# RSS.net
KiCad netlist of a schematic drawn in EAGLE
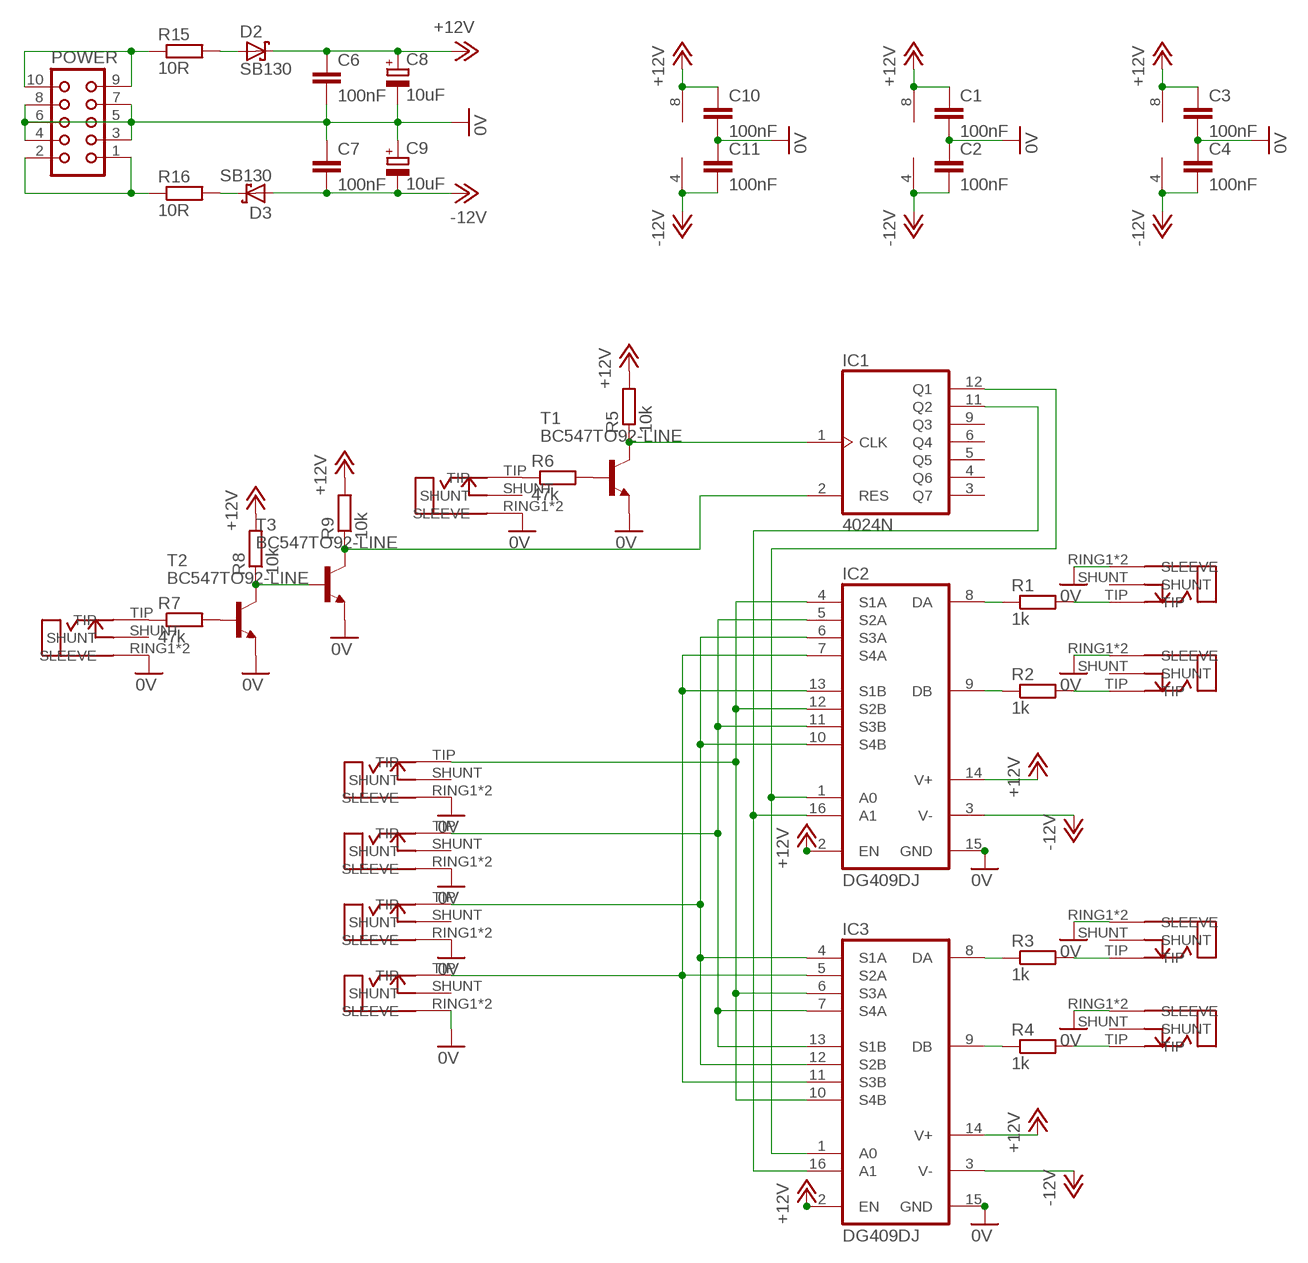
[diagram p0: schematic, sheet 1]

(export (version "E")
  (design (tool "Eeschema 10.0.6"))
  (components
    (comp (ref "C1")
      (value "100nF")
      (footprint "eagle-import:C025-024X044")
      (libsource (lib "eagle-import") (part "C-EU025-024X044"))
    )
    (comp (ref "C2")
      (value "100nF")
      (footprint "eagle-import:C025-024X044")
      (libsource (lib "eagle-import") (part "C-EU025-024X044"))
    )
    (comp (ref "C3")
      (value "100nF")
      (footprint "eagle-import:C025-024X044")
      (libsource (lib "eagle-import") (part "C-EU025-024X044"))
    )
    (comp (ref "C4")
      (value "100nF")
      (footprint "eagle-import:C025-024X044")
      (libsource (lib "eagle-import") (part "C-EU025-024X044"))
    )
    (comp (ref "C6")
      (value "100nF")
      (footprint "eagle-import:C025-024X044")
      (libsource (lib "eagle-import") (part "C-EU025-024X044"))
    )
    (comp (ref "C7")
      (value "100nF")
      (footprint "eagle-import:C025-024X044")
      (libsource (lib "eagle-import") (part "C-EU025-024X044"))
    )
    (comp (ref "C8")
      (value "10uF")
      (footprint "eagle-import:E2-5")
      (libsource (lib "eagle-import") (part "CPOL-EUE2-5"))
    )
    (comp (ref "C9")
      (value "10uF")
      (footprint "eagle-import:E2-5")
      (libsource (lib "eagle-import") (part "CPOL-EUE2-5"))
    )
    (comp (ref "C10")
      (value "100nF")
      (footprint "eagle-import:C025-024X044")
      (libsource (lib "eagle-import") (part "C-EU025-024X044"))
    )
    (comp (ref "C11")
      (value "100nF")
      (footprint "eagle-import:C025-024X044")
      (libsource (lib "eagle-import") (part "C-EU025-024X044"))
    )
    (comp (ref "CLOCK")
      (value "ERTHENVAR_3.5MM_JACKHOLES")
      (footprint "eagle-import:ERTHENVAR")
      (libsource (lib "eagle-import") (part "ERTHENVAR_3.5MM_JACKHOLES"))
    )
    (comp (ref "D2")
      (value "SB130")
      (footprint "eagle-import:DO41-7")
      (libsource (lib "eagle-import") (part "SB130DO-204AL"))
    )
    (comp (ref "D3")
      (value "SB130")
      (footprint "eagle-import:DO41-7")
      (libsource (lib "eagle-import") (part "SB130DO-204AL"))
    )
    (comp (ref "I/O1")
      (value "ERTHENVAR_3.5MM_JACKHOLES")
      (footprint "eagle-import:ERTHENVAR")
      (libsource (lib "eagle-import") (part "ERTHENVAR_3.5MM_JACKHOLES"))
    )
    (comp (ref "I/O2")
      (value "ERTHENVAR_3.5MM_JACKHOLES")
      (footprint "eagle-import:ERTHENVAR")
      (libsource (lib "eagle-import") (part "ERTHENVAR_3.5MM_JACKHOLES"))
    )
    (comp (ref "I/O3")
      (value "ERTHENVAR_3.5MM_JACKHOLES")
      (footprint "eagle-import:ERTHENVAR")
      (libsource (lib "eagle-import") (part "ERTHENVAR_3.5MM_JACKHOLES"))
    )
    (comp (ref "I/O4")
      (value "ERTHENVAR_3.5MM_JACKHOLES")
      (footprint "eagle-import:ERTHENVAR")
      (libsource (lib "eagle-import") (part "ERTHENVAR_3.5MM_JACKHOLES"))
    )
    (comp (ref "IC1")
      (value "4024N")
      (footprint "eagle-import:DIL14")
      (libsource (lib "eagle-import") (part "4024N"))
    )
    (comp (ref "IC2")
      (value "DG409DJ")
      (footprint "eagle-import:DIL16")
      (fields (field (name "MF") "INTERSIL"))
      (libsource (lib "eagle-import") (part "DG409DJ"))
    )
    (comp (ref "IC3")
      (value "DG409DJ")
      (footprint "eagle-import:DIL16")
      (fields (field (name "MF") "INTERSIL"))
      (libsource (lib "eagle-import") (part "DG409DJ"))
    )
    (comp (ref "IC4")
      (value "TL072")
      (footprint "eagle-import:DIL08")
      (libsource (lib "eagle-import") (part "TL072P"))
    )
    (comp (ref "IC5")
      (value "TL072")
      (footprint "eagle-import:DIL08")
      (libsource (lib "eagle-import") (part "TL072P"))
    )
    (comp (ref "IC6")
      (value "TL072")
      (footprint "eagle-import:DIL08")
      (libsource (lib "eagle-import") (part "TL072P"))
    )
    (comp (ref "O/I1")
      (value "ERTHENVAR_3.5MM_JACKHOLES")
      (footprint "eagle-import:ERTHENVAR")
      (libsource (lib "eagle-import") (part "ERTHENVAR_3.5MM_JACKHOLES"))
    )
    (comp (ref "O/I2")
      (value "ERTHENVAR_3.5MM_JACKHOLES")
      (footprint "eagle-import:ERTHENVAR")
      (libsource (lib "eagle-import") (part "ERTHENVAR_3.5MM_JACKHOLES"))
    )
    (comp (ref "O/I3")
      (value "ERTHENVAR_3.5MM_JACKHOLES")
      (footprint "eagle-import:ERTHENVAR")
      (libsource (lib "eagle-import") (part "ERTHENVAR_3.5MM_JACKHOLES"))
    )
    (comp (ref "O/I4")
      (value "ERTHENVAR_3.5MM_JACKHOLES")
      (footprint "eagle-import:ERTHENVAR")
      (libsource (lib "eagle-import") (part "ERTHENVAR_3.5MM_JACKHOLES"))
    )
    (comp (ref "POWER")
      (value "CON10L")
      (footprint "eagle-import:CON10L")
      (libsource (lib "eagle-import") (part "CON10L"))
    )
    (comp (ref "R1")
      (value "1k")
      (footprint "eagle-import:0207_9")
      (libsource (lib "eagle-import") (part "R-EU_0207/10"))
    )
    (comp (ref "R2")
      (value "1k")
      (footprint "eagle-import:0207_9")
      (libsource (lib "eagle-import") (part "R-EU_0207/10"))
    )
    (comp (ref "R3")
      (value "1k")
      (footprint "eagle-import:0207_9")
      (libsource (lib "eagle-import") (part "R-EU_0207/10"))
    )
    (comp (ref "R4")
      (value "1k")
      (footprint "eagle-import:0207_9")
      (libsource (lib "eagle-import") (part "R-EU_0207/10"))
    )
    (comp (ref "R5")
      (value "10k")
      (footprint "eagle-import:0207_9")
      (libsource (lib "eagle-import") (part "R-EU_0207/10"))
    )
    (comp (ref "R6")
      (value "47k")
      (footprint "eagle-import:0207_9")
      (libsource (lib "eagle-import") (part "R-EU_0207/10"))
    )
    (comp (ref "R7")
      (value "47k")
      (footprint "eagle-import:0207_9")
      (libsource (lib "eagle-import") (part "R-EU_0207/10"))
    )
    (comp (ref "R8")
      (value "10k")
      (footprint "eagle-import:0207_9")
      (libsource (lib "eagle-import") (part "R-EU_0207/10"))
    )
    (comp (ref "R9")
      (value "10k")
      (footprint "eagle-import:0207_9")
      (libsource (lib "eagle-import") (part "R-EU_0207/10"))
    )
    (comp (ref "R15")
      (value "10R")
      (footprint "eagle-import:0207_9")
      (libsource (lib "eagle-import") (part "R-EU_0207/10"))
    )
    (comp (ref "R16")
      (value "10R")
      (footprint "eagle-import:0207_9")
      (libsource (lib "eagle-import") (part "R-EU_0207/10"))
    )
    (comp (ref "SYNC/RESET")
      (value "ERTHENVAR_3.5MM_JACKHOLES")
      (footprint "eagle-import:ERTHENVAR")
      (libsource (lib "eagle-import") (part "ERTHENVAR_3.5MM_JACKHOLES"))
    )
    (comp (ref "T1")
      (value "BC547TO92-LINE")
      (footprint "eagle-import:TO92-LINE")
      (libsource (lib "eagle-import") (part "BC547TO92-LINE"))
    )
    (comp (ref "T2")
      (value "BC547TO92-LINE")
      (footprint "eagle-import:TO92-LINE")
      (libsource (lib "eagle-import") (part "BC547TO92-LINE"))
    )
    (comp (ref "T3")
      (value "BC547TO92-LINE")
      (footprint "eagle-import:TO92-LINE")
      (libsource (lib "eagle-import") (part "BC547TO92-LINE"))
    )
  )
  (nets
    (net (code "1") (name "+12V") (class "Default")
      (node (ref "C1") (pin "1") (pinfunction "1_1") (pintype "passive"))
      (node (ref "C10") (pin "1") (pinfunction "1_1") (pintype "passive"))
      (node (ref "C3") (pin "1") (pinfunction "1_1") (pintype "passive"))
      (node (ref "C6") (pin "1") (pinfunction "1_1") (pintype "passive"))
      (node (ref "C8") (pin "+") (pinfunction "+_+") (pintype "passive"))
      (node (ref "D2") (pin "C") (pinfunction "C_C") (pintype "passive"))
      (node (ref "IC2") (pin "14") (pinfunction "V+_14") (pintype "power_in"))
      (node (ref "IC2") (pin "2") (pinfunction "EN_2") (pintype "input"))
      (node (ref "IC3") (pin "14") (pinfunction "V+_14") (pintype "power_in"))
      (node (ref "IC3") (pin "2") (pinfunction "EN_2") (pintype "input"))
      (node (ref "IC4") (pin "8") (pinfunction "V+_8") (pintype "power_in"))
      (node (ref "IC5") (pin "8") (pinfunction "V+_8") (pintype "power_in"))
      (node (ref "IC6") (pin "8") (pinfunction "V+_8") (pintype "power_in"))
      (node (ref "R5") (pin "2") (pinfunction "2_2") (pintype "passive"))
      (node (ref "R8") (pin "2") (pinfunction "2_2") (pintype "passive"))
      (node (ref "R9") (pin "2") (pinfunction "2_2") (pintype "passive"))
    )
    (net (code "2") (name "-12V") (class "Default")
      (node (ref "C11") (pin "2") (pinfunction "2_2") (pintype "passive"))
      (node (ref "C2") (pin "2") (pinfunction "2_2") (pintype "passive"))
      (node (ref "C4") (pin "2") (pinfunction "2_2") (pintype "passive"))
      (node (ref "C7") (pin "2") (pinfunction "2_2") (pintype "passive"))
      (node (ref "C9") (pin "-") (pinfunction "-_-") (pintype "passive"))
      (node (ref "D3") (pin "A") (pinfunction "A_A") (pintype "passive"))
      (node (ref "IC2") (pin "3") (pinfunction "V-_3") (pintype "power_in"))
      (node (ref "IC3") (pin "3") (pinfunction "V-_3") (pintype "power_in"))
      (node (ref "IC4") (pin "4") (pinfunction "V-_4") (pintype "power_in"))
      (node (ref "IC5") (pin "4") (pinfunction "V-_4") (pintype "power_in"))
      (node (ref "IC6") (pin "4") (pinfunction "V-_4") (pintype "power_in"))
    )
    (net (code "3") (name "0V") (class "Default")
      (node (ref "C1") (pin "2") (pinfunction "2_2") (pintype "passive"))
      (node (ref "C10") (pin "2") (pinfunction "2_2") (pintype "passive"))
      (node (ref "C11") (pin "1") (pinfunction "1_1") (pintype "passive"))
      (node (ref "C2") (pin "1") (pinfunction "1_1") (pintype "passive"))
      (node (ref "C3") (pin "2") (pinfunction "2_2") (pintype "passive"))
      (node (ref "C4") (pin "1") (pinfunction "1_1") (pintype "passive"))
      (node (ref "C6") (pin "2") (pinfunction "2_2") (pintype "passive"))
      (node (ref "C7") (pin "1") (pinfunction "1_1") (pintype "passive"))
      (node (ref "C8") (pin "-") (pinfunction "-_-") (pintype "passive"))
      (node (ref "C9") (pin "+") (pinfunction "+_+") (pintype "passive"))
      (node (ref "CLOCK") (pin "RING1") (pinfunction "SLEEVE_RING1") (pintype "bidirectional"))
      (node (ref "CLOCK") (pin "RING2") (pinfunction "SLEEVE_RING2") (pintype "bidirectional"))
      (node (ref "I/O1") (pin "RING1") (pinfunction "SLEEVE_RING1") (pintype "bidirectional"))
      (node (ref "I/O1") (pin "RING2") (pinfunction "SLEEVE_RING2") (pintype "bidirectional"))
      (node (ref "I/O2") (pin "RING1") (pinfunction "SLEEVE_RING1") (pintype "bidirectional"))
      (node (ref "I/O2") (pin "RING2") (pinfunction "SLEEVE_RING2") (pintype "bidirectional"))
      (node (ref "I/O3") (pin "RING1") (pinfunction "SLEEVE_RING1") (pintype "bidirectional"))
      (node (ref "I/O3") (pin "RING2") (pinfunction "SLEEVE_RING2") (pintype "bidirectional"))
      (node (ref "I/O4") (pin "RING1") (pinfunction "SLEEVE_RING1") (pintype "bidirectional"))
      (node (ref "I/O4") (pin "RING2") (pinfunction "SLEEVE_RING2") (pintype "bidirectional"))
      (node (ref "IC2") (pin "15") (pinfunction "GND_15") (pintype "power_in"))
      (node (ref "IC3") (pin "15") (pinfunction "GND_15") (pintype "power_in"))
      (node (ref "O/I1") (pin "RING1") (pinfunction "SLEEVE_RING1") (pintype "bidirectional"))
      (node (ref "O/I1") (pin "RING2") (pinfunction "SLEEVE_RING2") (pintype "bidirectional"))
      (node (ref "O/I2") (pin "RING1") (pinfunction "SLEEVE_RING1") (pintype "bidirectional"))
      (node (ref "O/I2") (pin "RING2") (pinfunction "SLEEVE_RING2") (pintype "bidirectional"))
      (node (ref "O/I3") (pin "RING1") (pinfunction "SLEEVE_RING1") (pintype "bidirectional"))
      (node (ref "O/I3") (pin "RING2") (pinfunction "SLEEVE_RING2") (pintype "bidirectional"))
      (node (ref "O/I4") (pin "RING1") (pinfunction "SLEEVE_RING1") (pintype "bidirectional"))
      (node (ref "O/I4") (pin "RING2") (pinfunction "SLEEVE_RING2") (pintype "bidirectional"))
      (node (ref "POWER") (pin "3") (pinfunction "3_3") (pintype "passive"))
      (node (ref "POWER") (pin "4") (pinfunction "4_4") (pintype "passive"))
      (node (ref "POWER") (pin "5") (pinfunction "5_5") (pintype "passive"))
      (node (ref "POWER") (pin "6") (pinfunction "6_6") (pintype "passive"))
      (node (ref "POWER") (pin "7") (pinfunction "7_7") (pintype "passive"))
      (node (ref "POWER") (pin "8") (pinfunction "8_8") (pintype "passive"))
      (node (ref "SYNC/RESET") (pin "RING1") (pinfunction "SLEEVE_RING1") (pintype "bidirectional"))
      (node (ref "SYNC/RESET") (pin "RING2") (pinfunction "SLEEVE_RING2") (pintype "bidirectional"))
      (node (ref "T1") (pin "1") (pinfunction "E_1") (pintype "passive"))
      (node (ref "T2") (pin "1") (pinfunction "E_1") (pintype "passive"))
      (node (ref "T3") (pin "1") (pinfunction "E_1") (pintype "passive"))
    )
    (net (code "4") (name "Net-(CLOCK-PadTIP)") (class "Default")
      (node (ref "CLOCK") (pin "TIP") (pinfunction "TIP_TIP") (pintype "bidirectional"))
      (node (ref "R6") (pin "1") (pinfunction "1_1") (pintype "passive"))
    )
    (net (code "5") (name "Net-(D2-PadA)") (class "Default")
      (node (ref "D2") (pin "A") (pinfunction "A_A") (pintype "passive"))
      (node (ref "R15") (pin "2") (pinfunction "2_2") (pintype "passive"))
    )
    (net (code "6") (name "Net-(D3-PadC)") (class "Default")
      (node (ref "D3") (pin "C") (pinfunction "C_C") (pintype "passive"))
      (node (ref "R16") (pin "2") (pinfunction "2_2") (pintype "passive"))
    )
    (net (code "7") (name "Net-(I/O1-PadTIP)") (class "Default")
      (node (ref "I/O1") (pin "TIP") (pinfunction "TIP_TIP") (pintype "bidirectional"))
      (node (ref "R1") (pin "2") (pinfunction "2_2") (pintype "passive"))
    )
    (net (code "8") (name "Net-(I/O2-PadTIP)") (class "Default")
      (node (ref "I/O2") (pin "TIP") (pinfunction "TIP_TIP") (pintype "bidirectional"))
      (node (ref "R2") (pin "2") (pinfunction "2_2") (pintype "passive"))
    )
    (net (code "9") (name "Net-(I/O3-PadTIP)") (class "Default")
      (node (ref "I/O3") (pin "TIP") (pinfunction "TIP_TIP") (pintype "bidirectional"))
      (node (ref "R3") (pin "2") (pinfunction "2_2") (pintype "passive"))
    )
    (net (code "10") (name "Net-(I/O4-PadTIP)") (class "Default")
      (node (ref "I/O4") (pin "TIP") (pinfunction "TIP_TIP") (pintype "bidirectional"))
      (node (ref "R4") (pin "2") (pinfunction "2_2") (pintype "passive"))
    )
    (net (code "11") (name "Net-(IC1A-CLK)") (class "Default")
      (node (ref "IC1") (pin "1") (pinfunction "CLK_1") (pintype "input"))
      (node (ref "R5") (pin "1") (pinfunction "1_1") (pintype "passive"))
      (node (ref "T1") (pin "3") (pinfunction "C_3") (pintype "passive"))
    )
    (net (code "12") (name "Net-(IC1A-Q1)") (class "Default")
      (node (ref "IC1") (pin "12") (pinfunction "Q1_12") (pintype "output"))
      (node (ref "IC2") (pin "1") (pinfunction "A0_1") (pintype "input"))
      (node (ref "IC3") (pin "1") (pinfunction "A0_1") (pintype "input"))
    )
    (net (code "13") (name "Net-(IC1A-Q2)") (class "Default")
      (node (ref "IC1") (pin "11") (pinfunction "Q2_11") (pintype "output"))
      (node (ref "IC2") (pin "16") (pinfunction "A1_16") (pintype "input"))
      (node (ref "IC3") (pin "16") (pinfunction "A1_16") (pintype "input"))
    )
    (net (code "14") (name "Net-(IC1A-RES)") (class "Default")
      (node (ref "IC1") (pin "2") (pinfunction "RES_2") (pintype "input"))
      (node (ref "R9") (pin "1") (pinfunction "1_1") (pintype "passive"))
      (node (ref "T3") (pin "3") (pinfunction "C_3") (pintype "passive"))
    )
    (net (code "15") (name "Net-(IC2-DA)") (class "Default")
      (node (ref "IC2") (pin "8") (pinfunction "DA_8") (pintype "passive"))
      (node (ref "R1") (pin "1") (pinfunction "1_1") (pintype "passive"))
    )
    (net (code "16") (name "Net-(IC2-DB)") (class "Default")
      (node (ref "IC2") (pin "9") (pinfunction "DB_9") (pintype "passive"))
      (node (ref "R2") (pin "1") (pinfunction "1_1") (pintype "passive"))
    )
    (net (code "17") (name "Net-(IC2-S1A)") (class "Default")
      (node (ref "IC2") (pin "12") (pinfunction "S2B_12") (pintype "passive"))
      (node (ref "IC2") (pin "4") (pinfunction "S1A_4") (pintype "passive"))
      (node (ref "IC3") (pin "10") (pinfunction "S4B_10") (pintype "passive"))
      (node (ref "IC3") (pin "6") (pinfunction "S3A_6") (pintype "passive"))
      (node (ref "O/I1") (pin "TIP") (pinfunction "TIP_TIP") (pintype "bidirectional"))
    )
    (net (code "18") (name "Net-(IC2-S1B)") (class "Default")
      (node (ref "IC2") (pin "13") (pinfunction "S1B_13") (pintype "passive"))
      (node (ref "IC2") (pin "7") (pinfunction "S4A_7") (pintype "passive"))
      (node (ref "IC3") (pin "11") (pinfunction "S3B_11") (pintype "passive"))
      (node (ref "IC3") (pin "5") (pinfunction "S2A_5") (pintype "passive"))
      (node (ref "O/I4") (pin "TIP") (pinfunction "TIP_TIP") (pintype "bidirectional"))
    )
    (net (code "19") (name "Net-(IC2-S2A)") (class "Default")
      (node (ref "IC2") (pin "11") (pinfunction "S3B_11") (pintype "passive"))
      (node (ref "IC2") (pin "5") (pinfunction "S2A_5") (pintype "passive"))
      (node (ref "IC3") (pin "13") (pinfunction "S1B_13") (pintype "passive"))
      (node (ref "IC3") (pin "7") (pinfunction "S4A_7") (pintype "passive"))
      (node (ref "O/I2") (pin "TIP") (pinfunction "TIP_TIP") (pintype "bidirectional"))
    )
    (net (code "20") (name "Net-(IC2-S3A)") (class "Default")
      (node (ref "IC2") (pin "10") (pinfunction "S4B_10") (pintype "passive"))
      (node (ref "IC2") (pin "6") (pinfunction "S3A_6") (pintype "passive"))
      (node (ref "IC3") (pin "12") (pinfunction "S2B_12") (pintype "passive"))
      (node (ref "IC3") (pin "4") (pinfunction "S1A_4") (pintype "passive"))
      (node (ref "O/I3") (pin "TIP") (pinfunction "TIP_TIP") (pintype "bidirectional"))
    )
    (net (code "21") (name "Net-(IC3-DA)") (class "Default")
      (node (ref "IC3") (pin "8") (pinfunction "DA_8") (pintype "passive"))
      (node (ref "R3") (pin "1") (pinfunction "1_1") (pintype "passive"))
    )
    (net (code "22") (name "Net-(IC3-DB)") (class "Default")
      (node (ref "IC3") (pin "9") (pinfunction "DB_9") (pintype "passive"))
      (node (ref "R4") (pin "1") (pinfunction "1_1") (pintype "passive"))
    )
    (net (code "23") (name "Net-(POWER-Pad1)") (class "Default")
      (node (ref "POWER") (pin "1") (pinfunction "1_1") (pintype "passive"))
      (node (ref "POWER") (pin "2") (pinfunction "2_2") (pintype "passive"))
      (node (ref "R16") (pin "1") (pinfunction "1_1") (pintype "passive"))
    )
    (net (code "24") (name "Net-(POWER-Pad10)") (class "Default")
      (node (ref "POWER") (pin "10") (pinfunction "10_10") (pintype "passive"))
      (node (ref "POWER") (pin "9") (pinfunction "9_9") (pintype "passive"))
      (node (ref "R15") (pin "1") (pinfunction "1_1") (pintype "passive"))
    )
    (net (code "25") (name "Net-(R7-Pad1)") (class "Default")
      (node (ref "R7") (pin "1") (pinfunction "1_1") (pintype "passive"))
      (node (ref "SYNC/RESET") (pin "TIP") (pinfunction "TIP_TIP") (pintype "bidirectional"))
    )
    (net (code "26") (name "Net-(T1-B)") (class "Default")
      (node (ref "R6") (pin "2") (pinfunction "2_2") (pintype "passive"))
      (node (ref "T1") (pin "2") (pinfunction "B_2") (pintype "passive"))
    )
    (net (code "27") (name "Net-(T2-B)") (class "Default")
      (node (ref "R7") (pin "2") (pinfunction "2_2") (pintype "passive"))
      (node (ref "T2") (pin "2") (pinfunction "B_2") (pintype "passive"))
    )
    (net (code "28") (name "Net-(T2-C)") (class "Default")
      (node (ref "R8") (pin "1") (pinfunction "1_1") (pintype "passive"))
      (node (ref "T2") (pin "3") (pinfunction "C_3") (pintype "passive"))
      (node (ref "T3") (pin "2") (pinfunction "B_2") (pintype "passive"))
    )
    (net (code "29") (name "unconnected-(CLOCK-PadSHUNT)") (class "Default")
      (node (ref "CLOCK") (pin "SHUNT") (pinfunction "SHUNT_SHUNT") (pintype "bidirectional"))
    )
    (net (code "30") (name "unconnected-(I/O1-PadSHUNT)") (class "Default")
      (node (ref "I/O1") (pin "SHUNT") (pinfunction "SHUNT_SHUNT") (pintype "bidirectional"))
    )
    (net (code "31") (name "unconnected-(I/O2-PadSHUNT)") (class "Default")
      (node (ref "I/O2") (pin "SHUNT") (pinfunction "SHUNT_SHUNT") (pintype "bidirectional"))
    )
    (net (code "32") (name "unconnected-(I/O3-PadSHUNT)") (class "Default")
      (node (ref "I/O3") (pin "SHUNT") (pinfunction "SHUNT_SHUNT") (pintype "bidirectional"))
    )
    (net (code "33") (name "unconnected-(I/O4-PadSHUNT)") (class "Default")
      (node (ref "I/O4") (pin "SHUNT") (pinfunction "SHUNT_SHUNT") (pintype "bidirectional"))
    )
    (net (code "34") (name "unconnected-(IC1A-Q3-Pad9)") (class "Default")
      (node (ref "IC1") (pin "9") (pinfunction "Q3_9") (pintype "output"))
    )
    (net (code "35") (name "unconnected-(IC1A-Q4-Pad6)") (class "Default")
      (node (ref "IC1") (pin "6") (pinfunction "Q4_6") (pintype "output"))
    )
    (net (code "36") (name "unconnected-(IC1A-Q5-Pad5)") (class "Default")
      (node (ref "IC1") (pin "5") (pinfunction "Q5_5") (pintype "output"))
    )
    (net (code "37") (name "unconnected-(IC1A-Q6-Pad4)") (class "Default")
      (node (ref "IC1") (pin "4") (pinfunction "Q6_4") (pintype "output"))
    )
    (net (code "38") (name "unconnected-(IC1A-Q7-Pad3)") (class "Default")
      (node (ref "IC1") (pin "3") (pinfunction "Q7_3") (pintype "output"))
    )
    (net (code "39") (name "unconnected-(O/I1-PadSHUNT)") (class "Default")
      (node (ref "O/I1") (pin "SHUNT") (pinfunction "SHUNT_SHUNT") (pintype "bidirectional"))
    )
    (net (code "40") (name "unconnected-(O/I2-PadSHUNT)") (class "Default")
      (node (ref "O/I2") (pin "SHUNT") (pinfunction "SHUNT_SHUNT") (pintype "bidirectional"))
    )
    (net (code "41") (name "unconnected-(O/I3-PadSHUNT)") (class "Default")
      (node (ref "O/I3") (pin "SHUNT") (pinfunction "SHUNT_SHUNT") (pintype "bidirectional"))
    )
    (net (code "42") (name "unconnected-(O/I4-PadSHUNT)") (class "Default")
      (node (ref "O/I4") (pin "SHUNT") (pinfunction "SHUNT_SHUNT") (pintype "bidirectional"))
    )
    (net (code "43") (name "unconnected-(SYNC/RESET-PadSHUNT)") (class "Default")
      (node (ref "SYNC/RESET") (pin "SHUNT") (pinfunction "SHUNT_SHUNT") (pintype "bidirectional"))
    )
  )
)
